# accel-sd-gyro.net
KiCad netlist of a schematic drawn in EAGLE
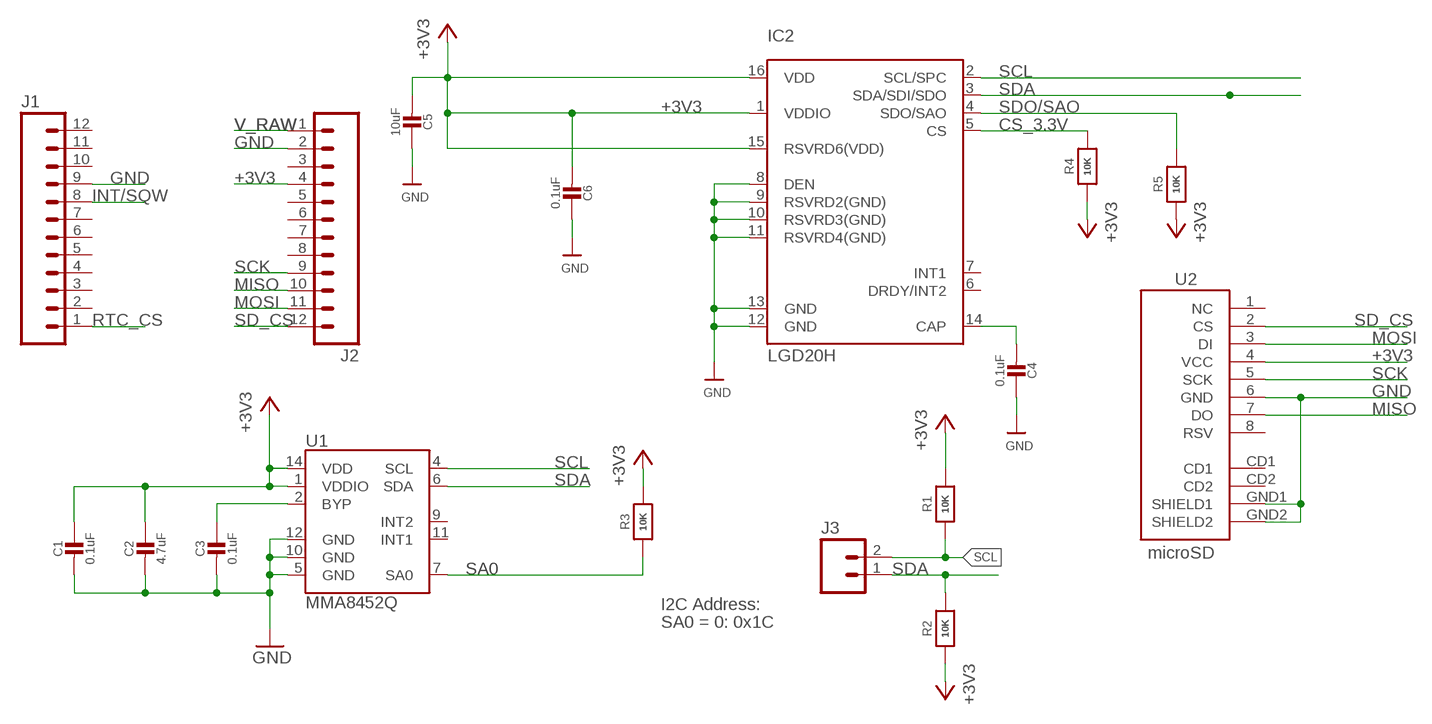
[diagram p0: schematic, sheet 1]

(export (version "E")
  (design (tool "Eeschema 10.0.6"))
  (components
    (comp (ref "C1")
      (value "0.1uF")
      (footprint "eagle-import:0805-NO")
      (libsource (lib "eagle-import") (part "CAP_CERAMIC0805-NOOUTLINE"))
    )
    (comp (ref "C2")
      (value "4.7uF")
      (footprint "eagle-import:0805-NO")
      (libsource (lib "eagle-import") (part "CAP_CERAMIC0805-NOOUTLINE"))
    )
    (comp (ref "C3")
      (value "0.1uF")
      (footprint "eagle-import:0805-NO")
      (libsource (lib "eagle-import") (part "CAP_CERAMIC0805-NOOUTLINE"))
    )
    (comp (ref "C4")
      (value "0.1uF")
      (footprint "eagle-import:0805-NO")
      (libsource (lib "eagle-import") (part "CAP_CERAMIC0805-NOOUTLINE"))
    )
    (comp (ref "C5")
      (value "10uF")
      (footprint "eagle-import:0805-NO")
      (libsource (lib "eagle-import") (part "CAP_CERAMIC0805-NOOUTLINE"))
    )
    (comp (ref "C6")
      (value "0.1uF")
      (footprint "eagle-import:0805-NO")
      (libsource (lib "eagle-import") (part "CAP_CERAMIC0805-NOOUTLINE"))
    )
    (comp (ref "IC2")
      (value "LGD20H")
      (footprint "eagle-import:L3GD20H_LGA16L")
      (libsource (lib "eagle-import") (part "GYRO_L3GD20H"))
    )
    (comp (ref "J1")
      (value "M12PTH")
      (footprint "eagle-import:1X12")
      (libsource (lib "eagle-import") (part "M12PTH"))
    )
    (comp (ref "J2")
      (value "M12PTH")
      (footprint "eagle-import:1X12")
      (libsource (lib "eagle-import") (part "M12PTH"))
    )
    (comp (ref "J3")
      (value "M02LOCK")
      (footprint "eagle-import:1X02_LOCK")
      (libsource (lib "eagle-import") (part "M02LOCK"))
    )
    (comp (ref "R1")
      (value "10K")
      (footprint "eagle-import:0805-NO")
      (libsource (lib "eagle-import") (part "RESISTOR0805_NOOUTLINE"))
    )
    (comp (ref "R2")
      (value "10K")
      (footprint "eagle-import:0805-NO")
      (libsource (lib "eagle-import") (part "RESISTOR0805_NOOUTLINE"))
    )
    (comp (ref "R3")
      (value "10K")
      (footprint "eagle-import:_0805MP")
      (libsource (lib "eagle-import") (part "RESISTOR_0805MP"))
    )
    (comp (ref "R4")
      (value "10K")
      (footprint "eagle-import:0805-NO")
      (libsource (lib "eagle-import") (part "RESISTOR0805_NOOUTLINE"))
    )
    (comp (ref "R5")
      (value "10K")
      (footprint "eagle-import:0805-NO")
      (libsource (lib "eagle-import") (part "RESISTOR0805_NOOUTLINE"))
    )
    (comp (ref "U1")
      (value "MMA8452Q")
      (footprint "eagle-import:QFN-16_0.5MM")
      (libsource (lib "eagle-import") (part "MMA8452Q"))
    )
    (comp (ref "U2")
      (value "microSD")
      (footprint "eagle-import:MICRO-SD-SOCKET-PP")
      (libsource (lib "eagle-import") (part "USD-SOCKETSMD"))
    )
  )
  (nets
    (net (code "1") (name "+3V3") (class "Default")
      (node (ref "C1") (pin "1") (pinfunction "1_1") (pintype "passive"))
      (node (ref "C2") (pin "1") (pinfunction "1_1") (pintype "passive"))
      (node (ref "C5") (pin "2") (pinfunction "2_2") (pintype "passive"))
      (node (ref "C6") (pin "2") (pinfunction "2_2") (pintype "passive"))
      (node (ref "IC2") (pin "1") (pinfunction "VDDIO_1") (pintype "power_in"))
      (node (ref "IC2") (pin "15") (pinfunction "RSVRD6(VDD)_15") (pintype "bidirectional"))
      (node (ref "IC2") (pin "16") (pinfunction "VDD_16") (pintype "bidirectional"))
      (node (ref "J2") (pin "4") (pinfunction "4_4") (pintype "passive"))
      (node (ref "R1") (pin "2") (pinfunction "2_2") (pintype "passive"))
      (node (ref "R2") (pin "1") (pinfunction "1_1") (pintype "passive"))
      (node (ref "R3") (pin "2") (pinfunction "2_2") (pintype "passive"))
      (node (ref "R4") (pin "1") (pinfunction "1_1") (pintype "passive"))
      (node (ref "R5") (pin "1") (pinfunction "1_1") (pintype "passive"))
      (node (ref "U1") (pin "1") (pinfunction "VDDIO_1") (pintype "bidirectional"))
      (node (ref "U1") (pin "14") (pinfunction "VDD_14") (pintype "bidirectional"))
      (node (ref "U2") (pin "4") (pinfunction "VCC_4") (pintype "bidirectional"))
    )
    (net (code "2") (name "/CS_3.3V") (class "Default")
      (node (ref "IC2") (pin "5") (pinfunction "CS_5") (pintype "bidirectional"))
      (node (ref "R4") (pin "2") (pinfunction "2_2") (pintype "passive"))
    )
    (net (code "3") (name "/INT{slash}SQW") (class "Default")
      (node (ref "J1") (pin "8") (pinfunction "8_8") (pintype "passive"))
    )
    (net (code "4") (name "/MISO") (class "Default")
      (node (ref "J2") (pin "10") (pinfunction "10_10") (pintype "passive"))
      (node (ref "U2") (pin "7") (pinfunction "DO_7") (pintype "bidirectional"))
    )
    (net (code "5") (name "/MOSI") (class "Default")
      (node (ref "J2") (pin "11") (pinfunction "11_11") (pintype "passive"))
      (node (ref "U2") (pin "3") (pinfunction "DI_3") (pintype "bidirectional"))
    )
    (net (code "6") (name "/RTC_CS") (class "Default")
      (node (ref "J1") (pin "1") (pinfunction "1_1") (pintype "passive"))
    )
    (net (code "7") (name "/SA0") (class "Default")
      (node (ref "R3") (pin "1") (pinfunction "1_1") (pintype "passive"))
      (node (ref "U1") (pin "7") (pinfunction "SA0_7") (pintype "bidirectional"))
    )
    (net (code "8") (name "/SCK") (class "Default")
      (node (ref "J2") (pin "9") (pinfunction "9_9") (pintype "passive"))
      (node (ref "U2") (pin "5") (pinfunction "SCK_5") (pintype "bidirectional"))
    )
    (net (code "9") (name "/SDA") (class "Default")
      (node (ref "IC2") (pin "3") (pinfunction "SDA/SDI/SDO_3") (pintype "bidirectional"))
      (node (ref "J3") (pin "1") (pinfunction "1_1") (pintype "passive"))
      (node (ref "R2") (pin "2") (pinfunction "2_2") (pintype "passive"))
      (node (ref "U1") (pin "6") (pinfunction "SDA_6") (pintype "bidirectional"))
    )
    (net (code "10") (name "/SDO{slash}SAO") (class "Default")
      (node (ref "IC2") (pin "4") (pinfunction "SDO/SAO_4") (pintype "bidirectional"))
      (node (ref "R5") (pin "2") (pinfunction "2_2") (pintype "passive"))
    )
    (net (code "11") (name "/SD_CS") (class "Default")
      (node (ref "J2") (pin "12") (pinfunction "12_12") (pintype "passive"))
      (node (ref "U2") (pin "2") (pinfunction "CS_2") (pintype "bidirectional"))
    )
    (net (code "12") (name "/V_RAW") (class "Default")
      (node (ref "J2") (pin "1") (pinfunction "1_1") (pintype "passive"))
    )
    (net (code "13") (name "GND") (class "Default")
      (node (ref "C1") (pin "2") (pinfunction "2_2") (pintype "passive"))
      (node (ref "C2") (pin "2") (pinfunction "2_2") (pintype "passive"))
      (node (ref "C3") (pin "2") (pinfunction "2_2") (pintype "passive"))
      (node (ref "C4") (pin "1") (pinfunction "1_1") (pintype "passive"))
      (node (ref "C5") (pin "1") (pinfunction "1_1") (pintype "passive"))
      (node (ref "C6") (pin "1") (pinfunction "1_1") (pintype "passive"))
      (node (ref "IC2") (pin "10") (pinfunction "RSVRD3(GND)_10") (pintype "bidirectional"))
      (node (ref "IC2") (pin "11") (pinfunction "RSVRD4(GND)_11") (pintype "bidirectional"))
      (node (ref "IC2") (pin "12") (pinfunction "GND_12") (pintype "bidirectional"))
      (node (ref "IC2") (pin "13") (pinfunction "GND_13") (pintype "bidirectional"))
      (node (ref "IC2") (pin "8") (pinfunction "DEN_8") (pintype "bidirectional"))
      (node (ref "IC2") (pin "9") (pinfunction "RSVRD2(GND)_9") (pintype "bidirectional"))
      (node (ref "J1") (pin "9") (pinfunction "9_9") (pintype "passive"))
      (node (ref "J2") (pin "2") (pinfunction "2_2") (pintype "passive"))
      (node (ref "U1") (pin "10") (pinfunction "GND_10") (pintype "bidirectional"))
      (node (ref "U1") (pin "12") (pinfunction "GND_12") (pintype "bidirectional"))
      (node (ref "U1") (pin "5") (pinfunction "GND_5") (pintype "bidirectional"))
      (node (ref "U2") (pin "6") (pinfunction "GND_6") (pintype "bidirectional"))
      (node (ref "U2") (pin "GND1") (pinfunction "SHIELD1_GND1") (pintype "bidirectional"))
      (node (ref "U2") (pin "GND2") (pinfunction "SHIELD2_GND2") (pintype "bidirectional"))
    )
    (net (code "14") (name "Net-(IC2-CAP)") (class "Default")
      (node (ref "C4") (pin "2") (pinfunction "2_2") (pintype "passive"))
      (node (ref "IC2") (pin "14") (pinfunction "CAP_14") (pintype "bidirectional"))
    )
    (net (code "15") (name "Net-(U1-BYP)") (class "Default")
      (node (ref "C3") (pin "1") (pinfunction "1_1") (pintype "passive"))
      (node (ref "U1") (pin "2") (pinfunction "BYP_2") (pintype "bidirectional"))
    )
    (net (code "16") (name "SCL") (class "Default")
      (node (ref "IC2") (pin "2") (pinfunction "SCL/SPC_2") (pintype "bidirectional"))
      (node (ref "J3") (pin "2") (pinfunction "2_2") (pintype "passive"))
      (node (ref "R1") (pin "1") (pinfunction "1_1") (pintype "passive"))
      (node (ref "U1") (pin "4") (pinfunction "SCL_4") (pintype "bidirectional"))
    )
    (net (code "17") (name "unconnected-(IC2-DRDY{slash}INT2-Pad6)") (class "Default")
      (node (ref "IC2") (pin "6") (pinfunction "DRDY/INT2_6") (pintype "bidirectional"))
    )
    (net (code "18") (name "unconnected-(IC2-INT1-Pad7)") (class "Default")
      (node (ref "IC2") (pin "7") (pinfunction "INT1_7") (pintype "bidirectional"))
    )
    (net (code "19") (name "unconnected-(J1-Pad2)") (class "Default")
      (node (ref "J1") (pin "2") (pinfunction "2_2") (pintype "passive"))
    )
    (net (code "20") (name "unconnected-(J1-Pad3)") (class "Default")
      (node (ref "J1") (pin "3") (pinfunction "3_3") (pintype "passive"))
    )
    (net (code "21") (name "unconnected-(J1-Pad4)") (class "Default")
      (node (ref "J1") (pin "4") (pinfunction "4_4") (pintype "passive"))
    )
    (net (code "22") (name "unconnected-(J1-Pad5)") (class "Default")
      (node (ref "J1") (pin "5") (pinfunction "5_5") (pintype "passive"))
    )
    (net (code "23") (name "unconnected-(J1-Pad6)") (class "Default")
      (node (ref "J1") (pin "6") (pinfunction "6_6") (pintype "passive"))
    )
    (net (code "24") (name "unconnected-(J1-Pad7)") (class "Default")
      (node (ref "J1") (pin "7") (pinfunction "7_7") (pintype "passive"))
    )
    (net (code "25") (name "unconnected-(J1-Pad10)") (class "Default")
      (node (ref "J1") (pin "10") (pinfunction "10_10") (pintype "passive"))
    )
    (net (code "26") (name "unconnected-(J1-Pad11)") (class "Default")
      (node (ref "J1") (pin "11") (pinfunction "11_11") (pintype "passive"))
    )
    (net (code "27") (name "unconnected-(J1-Pad12)") (class "Default")
      (node (ref "J1") (pin "12") (pinfunction "12_12") (pintype "passive"))
    )
    (net (code "28") (name "unconnected-(J2-Pad3)") (class "Default")
      (node (ref "J2") (pin "3") (pinfunction "3_3") (pintype "passive"))
    )
    (net (code "29") (name "unconnected-(J2-Pad5)") (class "Default")
      (node (ref "J2") (pin "5") (pinfunction "5_5") (pintype "passive"))
    )
    (net (code "30") (name "unconnected-(J2-Pad6)") (class "Default")
      (node (ref "J2") (pin "6") (pinfunction "6_6") (pintype "passive"))
    )
    (net (code "31") (name "unconnected-(J2-Pad7)") (class "Default")
      (node (ref "J2") (pin "7") (pinfunction "7_7") (pintype "passive"))
    )
    (net (code "32") (name "unconnected-(J2-Pad8)") (class "Default")
      (node (ref "J2") (pin "8") (pinfunction "8_8") (pintype "passive"))
    )
    (net (code "33") (name "unconnected-(U1-INT1-Pad11)") (class "Default")
      (node (ref "U1") (pin "11") (pinfunction "INT1_11") (pintype "bidirectional"))
    )
    (net (code "34") (name "unconnected-(U1-INT2-Pad9)") (class "Default")
      (node (ref "U1") (pin "9") (pinfunction "INT2_9") (pintype "bidirectional"))
    )
    (net (code "35") (name "unconnected-(U2-NC-Pad1)") (class "Default")
      (node (ref "U2") (pin "1") (pinfunction "NC_1") (pintype "bidirectional"))
    )
    (net (code "36") (name "unconnected-(U2-PadCD1)") (class "Default")
      (node (ref "U2") (pin "CD1") (pinfunction "CD1_CD1") (pintype "bidirectional"))
    )
    (net (code "37") (name "unconnected-(U2-PadCD2)") (class "Default")
      (node (ref "U2") (pin "CD2") (pinfunction "CD2_CD2") (pintype "bidirectional"))
    )
    (net (code "38") (name "unconnected-(U2-RSV-Pad8)") (class "Default")
      (node (ref "U2") (pin "8") (pinfunction "RSV_8") (pintype "bidirectional"))
    )
  )
)
